# 1-Schematic_Canokey-NFC-C.net
KiCad netlist of a schematic drawn in EasyEDA
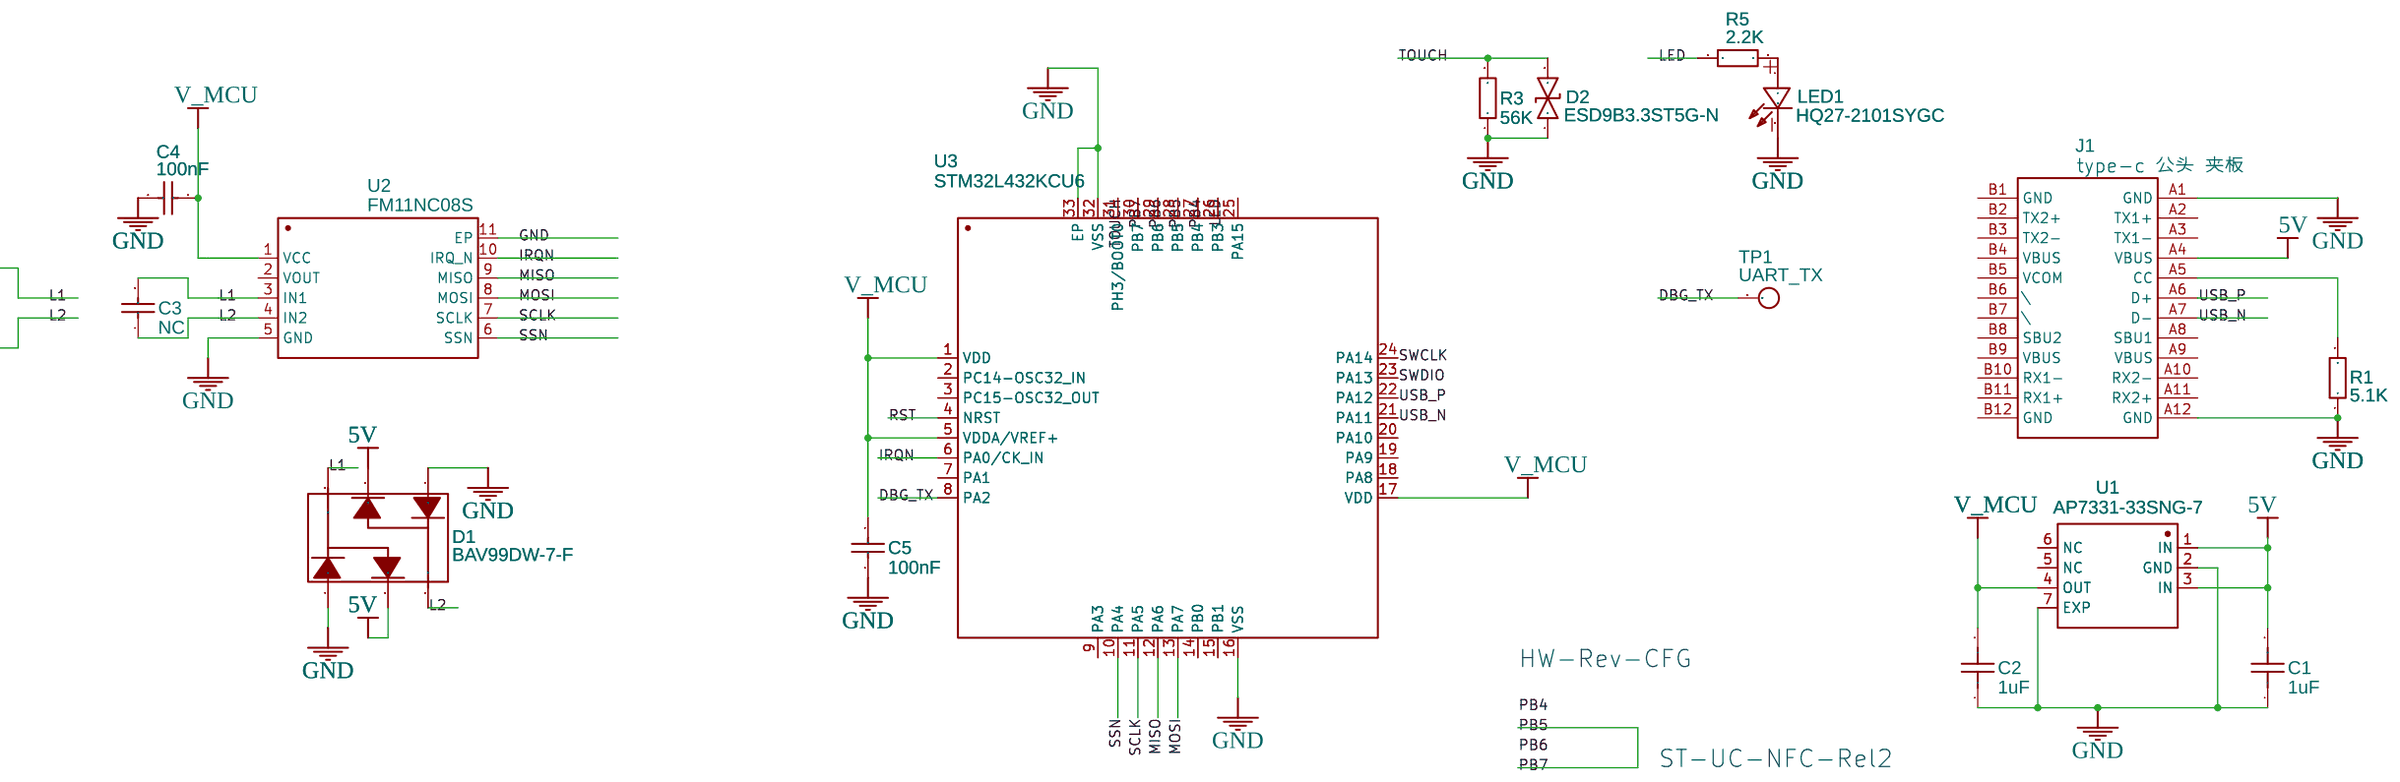
[diagram p0: schematic sheet]

(export (version "E")
  (design (tool "Eeschema 10.0.6"))
  (components
    (comp (ref "C1")
      (value "1uF")
      (fields
        (field (name "BOM_Manufacturer Part") "CL05A105KA5NQNC")
        (field (name "BOM_Supplier Part") "C52923")
      )
      (libsource (lib "") (part "CL05A105KA5NQNC"))
    )
    (comp (ref "C2")
      (value "1uF")
      (fields
        (field (name "BOM_Manufacturer Part") "CL05A105KA5NQNC")
        (field (name "BOM_Supplier Part") "C52923")
      )
      (libsource (lib "") (part "CL05A105KA5NQNC"))
    )
    (comp (ref "C3")
      (value "NC")
      (fields
        (field (name "BOM_Manufacturer Part") "0402CG560J500NT")
        (field (name "BOM_Supplier Part") "C1572")
      )
      (libsource (lib "") (part "0402CG560J500NT"))
    )
    (comp (ref "C4")
      (value "100nF")
      (fields
        (field (name "BOM_Manufacturer Part") "CL05B104KO5NNNC")
        (field (name "BOM_Supplier Part") "C1525")
      )
      (libsource (lib "") (part "CL05B104KO5NNNC_1"))
    )
    (comp (ref "C5")
      (value "100nF")
      (fields
        (field (name "BOM_Manufacturer Part") "CL05B104KO5NNNC")
        (field (name "BOM_Supplier Part") "C1525")
      )
      (libsource (lib "") (part "CL05B104KO5NNNC"))
    )
    (comp (ref "D1")
      (value "BAV99DW-7-F")
      (fields (field (name "BOM_Supplier Part") "C150465"))
      (libsource (lib "") (part "BAV99DW-7-F"))
    )
    (comp (ref "D2")
      (value "ESD9B3.3ST5G-N")
      (fields (field (name "BOM_Supplier Part") "C316039"))
      (libsource (lib "") (part "ESD9B3.3ST5G-N"))
    )
    (comp (ref "J1") (value "type-c 公头 夹板") (libsource (lib "") (part "type-c 公头 夹板")))
    (comp (ref "LED1")
      (value "HQ27-2101SYGC")
      (fields (field (name "BOM_Supplier Part") "C258853"))
      (libsource (lib "") (part "HQ27-2101SYGC"))
    )
    (comp (ref "R1")
      (value "5.1K")
      (fields
        (field (name "BOM_Manufacturer Part") "0402WGF5101TCE")
        (field (name "BOM_Supplier Part") "C25905")
      )
      (libsource (lib "") (part "0402WGF5101TCE"))
    )
    (comp (ref "R3")
      (value "56K")
      (fields
        (field (name "BOM_Manufacturer Part") "0402WGF5602TCE")
        (field (name "BOM_Supplier Part") "C25796")
      )
      (libsource (lib "") (part "0402WGF5602TCE"))
    )
    (comp (ref "R5")
      (value "2.2K")
      (fields
        (field (name "BOM_Manufacturer Part") "0402WGF2201TCE")
        (field (name "BOM_Supplier Part") "C25879")
      )
      (libsource (lib "") (part "0402WGF2201TCE"))
    )
    (comp (ref "TP1") (value "UART_TX") (libsource (lib "") (part "Unknown_530_-50")))
    (comp (ref "U1")
      (value "AP7331-33SNG-7")
      (fields (field (name "BOM_Supplier Part") "C150446"))
      (libsource (lib "") (part "AP7331-33SNG-7"))
    )
    (comp (ref "U2")
      (value "FM11NC08S")
      (fields (field (name "BOM_Supplier Part") "C182885"))
      (libsource (lib "") (part "Unknown_-160_-60"))
    )
    (comp (ref "U3")
      (value "STM32L432KCU6")
      (fields
        (field (name "BOM_Manufacturer Part") "STM32L432KBU6")
        (field (name "BOM_Supplier Part") "C94784")
      )
      (libsource (lib "") (part "Unknown_235_15"))
    )
  )
  (nets
    (net (code "1") (name "/DBG_TX") (class "Default")
      (node (ref "TP1") (pin "P$1") (pinfunction "P$1_P$1") (pintype "bidirectional"))
      (node (ref "U3") (pin "8") (pinfunction "PA2_8") (pintype "unspecified"))
    )
    (net (code "2") (name "/IRQN") (class "Default")
      (node (ref "U2") (pin "10") (pinfunction "IRQ_N_10") (pintype "unspecified"))
      (node (ref "U3") (pin "6") (pinfunction "PA0/CK_IN_6") (pintype "unspecified"))
    )
    (net (code "3") (name "/L1") (class "Default")
      (node (ref "C3") (pin "1") (pinfunction "1_1") (pintype "input"))
      (node (ref "C3") (pin "2") (pinfunction "2_2") (pintype "input"))
      (node (ref "D1") (pin "3") (pinfunction "3_3") (pintype "unspecified"))
      (node (ref "D1") (pin "6") (pinfunction "6_6") (pintype "unspecified"))
      (node (ref "U2") (pin "3") (pinfunction "IN1_3") (pintype "unspecified"))
      (node (ref "U2") (pin "4") (pinfunction "IN2_4") (pintype "unspecified"))
    )
    (net (code "4") (name "/LED") (class "Default")
      (node (ref "R5") (pin "1") (pinfunction "1_1") (pintype "input"))
      (node (ref "U3") (pin "26") (pinfunction "PB3_26") (pintype "unspecified"))
    )
    (net (code "5") (name "/MISO") (class "Default")
      (node (ref "U2") (pin "9") (pinfunction "MISO_9") (pintype "unspecified"))
      (node (ref "U3") (pin "12") (pinfunction "PA6_12") (pintype "unspecified"))
    )
    (net (code "6") (name "/MOSI") (class "Default")
      (node (ref "U2") (pin "8") (pinfunction "MOSI_8") (pintype "unspecified"))
      (node (ref "U3") (pin "13") (pinfunction "PA7_13") (pintype "unspecified"))
    )
    (net (code "7") (name "/PB4") (class "Default")
      (node (ref "U3") (pin "27") (pinfunction "PB4_27") (pintype "unspecified"))
    )
    (net (code "8") (name "/PB5") (class "Default")
      (node (ref "U3") (pin "28") (pinfunction "PB5_28") (pintype "unspecified"))
      (node (ref "U3") (pin "30") (pinfunction "PB7_30") (pintype "unspecified"))
    )
    (net (code "9") (name "/PB6") (class "Default")
      (node (ref "U3") (pin "29") (pinfunction "PB6_29") (pintype "unspecified"))
    )
    (net (code "10") (name "/RST") (class "Default")
      (node (ref "U3") (pin "4") (pinfunction "NRST_4") (pintype "unspecified"))
    )
    (net (code "11") (name "/SCLK") (class "Default")
      (node (ref "U2") (pin "7") (pinfunction "SCLK_7") (pintype "unspecified"))
      (node (ref "U3") (pin "11") (pinfunction "PA5_11") (pintype "unspecified"))
    )
    (net (code "12") (name "/SSN") (class "Default")
      (node (ref "U2") (pin "6") (pinfunction "SSN_6") (pintype "unspecified"))
      (node (ref "U3") (pin "10") (pinfunction "PA4_10") (pintype "unspecified"))
    )
    (net (code "13") (name "/SWCLK") (class "Default")
      (node (ref "U3") (pin "24") (pinfunction "PA14_24") (pintype "unspecified"))
    )
    (net (code "14") (name "/SWDIO") (class "Default")
      (node (ref "U3") (pin "23") (pinfunction "PA13_23") (pintype "unspecified"))
    )
    (net (code "15") (name "/TOUCH") (class "Default")
      (node (ref "D2") (pin "2") (pinfunction "2_2") (pintype "unspecified"))
      (node (ref "R3") (pin "2") (pinfunction "2_2") (pintype "input"))
      (node (ref "U3") (pin "31") (pinfunction "PH3/BOOT0_31") (pintype "unspecified"))
    )
    (net (code "16") (name "/USB_N") (class "Default")
      (node (ref "J1") (pin "A7") (pinfunction "D-_A7") (pintype "unspecified"))
      (node (ref "U3") (pin "21") (pinfunction "PA11_21") (pintype "unspecified"))
    )
    (net (code "17") (name "/USB_P") (class "Default")
      (node (ref "J1") (pin "A6") (pinfunction "D+_A6") (pintype "unspecified"))
      (node (ref "U3") (pin "22") (pinfunction "PA12_22") (pintype "unspecified"))
    )
    (net (code "18") (name "5V") (class "Default")
      (node (ref "C1") (pin "2") (pinfunction "2_2") (pintype "unspecified"))
      (node (ref "D1") (pin "2") (pinfunction "2_2") (pintype "unspecified"))
      (node (ref "D1") (pin "5") (pinfunction "5_5") (pintype "unspecified"))
      (node (ref "J1") (pin "A4") (pinfunction "VBUS_A4") (pintype "unspecified"))
      (node (ref "U1") (pin "1") (pinfunction "IN_1") (pintype "unspecified"))
      (node (ref "U1") (pin "3") (pinfunction "IN_3") (pintype "unspecified"))
    )
    (net (code "19") (name "GND") (class "Default")
      (node (ref "C1") (pin "1") (pinfunction "1_1") (pintype "unspecified"))
      (node (ref "C2") (pin "1") (pinfunction "1_1") (pintype "unspecified"))
      (node (ref "C4") (pin "2") (pinfunction "2_2") (pintype "input"))
      (node (ref "C5") (pin "1") (pinfunction "1_1") (pintype "input"))
      (node (ref "D1") (pin "1") (pinfunction "1_1") (pintype "unspecified"))
      (node (ref "D1") (pin "4") (pinfunction "4_4") (pintype "unspecified"))
      (node (ref "D2") (pin "1") (pinfunction "1_1") (pintype "unspecified"))
      (node (ref "J1") (pin "A1") (pinfunction "GND_A1") (pintype "unspecified"))
      (node (ref "J1") (pin "A12") (pinfunction "GND_A12") (pintype "unspecified"))
      (node (ref "LED1") (pin "2") (pinfunction "2_2") (pintype "unspecified"))
      (node (ref "R1") (pin "1") (pinfunction "1_1") (pintype "input"))
      (node (ref "R3") (pin "1") (pinfunction "1_1") (pintype "input"))
      (node (ref "U1") (pin "2") (pinfunction "GND_2") (pintype "unspecified"))
      (node (ref "U1") (pin "7") (pinfunction "EXP_7") (pintype "unspecified"))
      (node (ref "U2") (pin "11") (pinfunction "EP_11") (pintype "unspecified"))
      (node (ref "U2") (pin "5") (pinfunction "GND_5") (pintype "unspecified"))
      (node (ref "U3") (pin "16") (pinfunction "VSS_16") (pintype "unspecified"))
      (node (ref "U3") (pin "32") (pinfunction "VSS_32") (pintype "unspecified"))
      (node (ref "U3") (pin "33") (pinfunction "EP_33") (pintype "unspecified"))
    )
    (net (code "20") (name "Net-(J1-CC)") (class "Default")
      (node (ref "J1") (pin "A5") (pinfunction "CC_A5") (pintype "unspecified"))
      (node (ref "R1") (pin "2") (pinfunction "2_2") (pintype "input"))
    )
    (net (code "21") (name "Net-(LED1-Pad1)") (class "Default")
      (node (ref "LED1") (pin "1") (pinfunction "1_1") (pintype "unspecified"))
      (node (ref "R5") (pin "2") (pinfunction "2_2") (pintype "input"))
    )
    (net (code "22") (name "V_MCU") (class "Default")
      (node (ref "C2") (pin "2") (pinfunction "2_2") (pintype "unspecified"))
      (node (ref "C4") (pin "1") (pinfunction "1_1") (pintype "input"))
      (node (ref "C5") (pin "2") (pinfunction "2_2") (pintype "input"))
      (node (ref "U1") (pin "4") (pinfunction "OUT_4") (pintype "unspecified"))
      (node (ref "U2") (pin "1") (pinfunction "VCC_1") (pintype "unspecified"))
      (node (ref "U3") (pin "1") (pinfunction "VDD_1") (pintype "unspecified"))
      (node (ref "U3") (pin "17") (pinfunction "VDD_17") (pintype "unspecified"))
      (node (ref "U3") (pin "5") (pinfunction "VDDA/VREF+_5") (pintype "unspecified"))
    )
    (net (code "23") (name "unconnected-(J1-GND-PadB1)") (class "Default")
      (node (ref "J1") (pin "B1") (pinfunction "GND_B1") (pintype "unspecified"))
    )
    (net (code "24") (name "unconnected-(J1-GND-PadB12)") (class "Default")
      (node (ref "J1") (pin "B12") (pinfunction "GND_B12") (pintype "unspecified"))
    )
    (net (code "25") (name "unconnected-(J1-RX1+-PadB11)") (class "Default")
      (node (ref "J1") (pin "B11") (pinfunction "RX1+_B11") (pintype "unspecified"))
    )
    (net (code "26") (name "unconnected-(J1-RX1--PadB10)") (class "Default")
      (node (ref "J1") (pin "B10") (pinfunction "RX1-_B10") (pintype "unspecified"))
    )
    (net (code "27") (name "unconnected-(J1-RX2+-PadA11)") (class "Default")
      (node (ref "J1") (pin "A11") (pinfunction "RX2+_A11") (pintype "unspecified"))
    )
    (net (code "28") (name "unconnected-(J1-RX2--PadA10)") (class "Default")
      (node (ref "J1") (pin "A10") (pinfunction "RX2-_A10") (pintype "unspecified"))
    )
    (net (code "29") (name "unconnected-(J1-SBU1-PadA8)") (class "Default")
      (node (ref "J1") (pin "A8") (pinfunction "SBU1_A8") (pintype "unspecified"))
    )
    (net (code "30") (name "unconnected-(J1-SBU2-PadB8)") (class "Default")
      (node (ref "J1") (pin "B8") (pinfunction "SBU2_B8") (pintype "unspecified"))
    )
    (net (code "31") (name "unconnected-(J1-TX1+-PadA2)") (class "Default")
      (node (ref "J1") (pin "A2") (pinfunction "TX1+_A2") (pintype "unspecified"))
    )
    (net (code "32") (name "unconnected-(J1-TX1--PadA3)") (class "Default")
      (node (ref "J1") (pin "A3") (pinfunction "TX1-_A3") (pintype "unspecified"))
    )
    (net (code "33") (name "unconnected-(J1-TX2+-PadB2)") (class "Default")
      (node (ref "J1") (pin "B2") (pinfunction "TX2+_B2") (pintype "unspecified"))
    )
    (net (code "34") (name "unconnected-(J1-TX2--PadB3)") (class "Default")
      (node (ref "J1") (pin "B3") (pinfunction "TX2-_B3") (pintype "unspecified"))
    )
    (net (code "35") (name "unconnected-(J1-VBUS-PadA9)") (class "Default")
      (node (ref "J1") (pin "A9") (pinfunction "VBUS_A9") (pintype "unspecified"))
    )
    (net (code "36") (name "unconnected-(J1-VBUS-PadB4)") (class "Default")
      (node (ref "J1") (pin "B4") (pinfunction "VBUS_B4") (pintype "unspecified"))
    )
    (net (code "37") (name "unconnected-(J1-VBUS-PadB9)") (class "Default")
      (node (ref "J1") (pin "B9") (pinfunction "VBUS_B9") (pintype "unspecified"))
    )
    (net (code "38") (name "unconnected-(J1-VCOM-PadB5)") (class "Default")
      (node (ref "J1") (pin "B5") (pinfunction "VCOM_B5") (pintype "unspecified"))
    )
    (net (code "39") (name "unconnected-(J1-\\-PadB6)") (class "Default")
      (node (ref "J1") (pin "B6") (pinfunction "\\_B6") (pintype "unspecified"))
    )
    (net (code "40") (name "unconnected-(J1-\\-PadB7)") (class "Default")
      (node (ref "J1") (pin "B7") (pinfunction "\\_B7") (pintype "unspecified"))
    )
    (net (code "41") (name "unconnected-(U1-NC-Pad5)") (class "Default")
      (node (ref "U1") (pin "5") (pinfunction "NC_5") (pintype "unspecified"))
    )
    (net (code "42") (name "unconnected-(U1-NC-Pad6)") (class "Default")
      (node (ref "U1") (pin "6") (pinfunction "NC_6") (pintype "unspecified"))
    )
    (net (code "43") (name "unconnected-(U2-VOUT-Pad2)") (class "Default")
      (node (ref "U2") (pin "2") (pinfunction "VOUT_2") (pintype "unspecified"))
    )
    (net (code "44") (name "unconnected-(U3-PA1-Pad7)") (class "Default")
      (node (ref "U3") (pin "7") (pinfunction "PA1_7") (pintype "unspecified"))
    )
    (net (code "45") (name "unconnected-(U3-PA3-Pad9)") (class "Default")
      (node (ref "U3") (pin "9") (pinfunction "PA3_9") (pintype "unspecified"))
    )
    (net (code "46") (name "unconnected-(U3-PA8-Pad18)") (class "Default")
      (node (ref "U3") (pin "18") (pinfunction "PA8_18") (pintype "unspecified"))
    )
    (net (code "47") (name "unconnected-(U3-PA9-Pad19)") (class "Default")
      (node (ref "U3") (pin "19") (pinfunction "PA9_19") (pintype "unspecified"))
    )
    (net (code "48") (name "unconnected-(U3-PA10-Pad20)") (class "Default")
      (node (ref "U3") (pin "20") (pinfunction "PA10_20") (pintype "unspecified"))
    )
    (net (code "49") (name "unconnected-(U3-PA15-Pad25)") (class "Default")
      (node (ref "U3") (pin "25") (pinfunction "PA15_25") (pintype "unspecified"))
    )
    (net (code "50") (name "unconnected-(U3-PB0-Pad14)") (class "Default")
      (node (ref "U3") (pin "14") (pinfunction "PB0_14") (pintype "unspecified"))
    )
    (net (code "51") (name "unconnected-(U3-PB1-Pad15)") (class "Default")
      (node (ref "U3") (pin "15") (pinfunction "PB1_15") (pintype "unspecified"))
    )
    (net (code "52") (name "unconnected-(U3-PC14-OSC32_IN-Pad2)") (class "Default")
      (node (ref "U3") (pin "2") (pinfunction "PC14-OSC32_IN_2") (pintype "unspecified"))
    )
    (net (code "53") (name "unconnected-(U3-PC15-OSC32_OUT-Pad3)") (class "Default")
      (node (ref "U3") (pin "3") (pinfunction "PC15-OSC32_OUT_3") (pintype "unspecified"))
    )
  )
)
